# CAN.net
KiCad netlist of a schematic drawn in Altium Designer
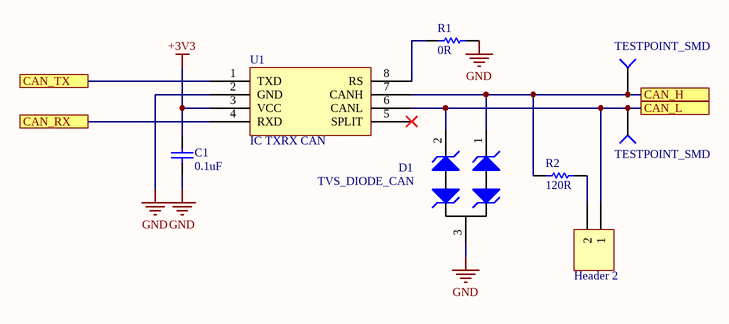
[diagram p0: CAN.SchDoc]

(export (version "E")
  (design (tool "Eeschema 10.0.6"))
  (components
    (comp (ref "1")
      (value "Header 2")
      (footprint "HDR1X2")
      (description "Header, 2-Pin")
      (fields (field (name "PUBLISHER") "Altium Limited"))
      (libsource (lib "Miscellaneous Connectors") (part "Header 2"))
    )
    (comp (ref "C1")
      (value "0.1uF")
      (footprint "CAPC0603(1608)55_N")
      (description "CAP CER 0.1UF 16V X7R 0603")
      (fields (field (name "PART NUMBER") "CC0603KRX7R7BB104") (field (name "MANUFACTURER") "Yageo"))
      (libsource (lib "UWRT_Schematic_Library_2019") (part "CAP_0.1uF_16V_0603"))
    )
    (comp (ref "D1")
      (value "TVS_DIODE_CAN")
      (footprint "TVS_DIODE_CAN")
      (description "TVS DIODE 24V 41V SOT323-3")
      (fields (field (name "PART NUMBER") "PESD2CAN,215") (field (name "MANUFACTURER") "Nexperia USA Inc."))
      (libsource (lib "UWRT_Schematic_Library_2019") (part "TVS_DIODE_CAN"))
    )
    (comp (ref "R1")
      (value "0R")
      (footprint "RESC0603(1608)_N")
      (description "RES SMD 0 OHM JUMPER 1/10W 0603")
      (fields (field (name "MANUFACTURER") "Yageo") (field (name "Comment") "RES_0R_0603"))
      (libsource (lib "UWRT_Schematic_Library_2019") (part "RES_0R_0603"))
    )
    (comp (ref "R2")
      (value "120R")
      (footprint "RESC0603(1608)_N")
      (description "RES SMD 120 OHM 5% 1/10W 0603")
      (fields (field (name "MANUFACTURER") "Yageo") (field (name "TOLERANCE") "5%"))
      (libsource (lib "UWRT_Schematic_Library_2019") (part "RES_120R_0603"))
    )
    (comp (ref "TP1")
      (value "TESTPOINT_SMD")
      (footprint "TESTPOINT")
      (libsource (lib "UWRT_Schematic_Library_2019") (part "TESTPOINT_SMD"))
    )
    (comp (ref "TP2")
      (value "TESTPOINT_SMD")
      (footprint "TESTPOINT")
      (libsource (lib "UWRT_Schematic_Library_2019") (part "TESTPOINT_SMD"))
    )
    (comp (ref "U1")
      (value "IC TXRX CAN")
      (footprint "LTC2875")
      (description "IC TXRX CAN 4MBPS 8SO")
      (fields
        (field (name "MANUFACTURER") "Linear Technologies")
        (field (name "PART NUMBER") "LTC2875IS8#PBF")
      )
      (libsource (lib "UWRT_Schematic_Library_2019") (part "LTC2875"))
    )
  )
  (nets
    (net (code "1") (name "+3V3") (class "Default")
      (node (ref "C1") (pin "2") (pinfunction "2_2") (pintype "passive"))
      (node (ref "U1") (pin "3") (pinfunction "VCC_3") (pintype "passive"))
    )
    (net (code "2") (name "/CAN_H") (class "Default")
      (node (ref "D1") (pin "1") (pinfunction "1_1") (pintype "passive"))
      (node (ref "R2") (pin "1") (pinfunction "1_1") (pintype "passive"))
      (node (ref "TP1") (pin "1") (pinfunction "=value_1") (pintype "passive"))
      (node (ref "U1") (pin "7") (pinfunction "CANH_7") (pintype "passive"))
    )
    (net (code "3") (name "/CAN_L") (class "Default")
      (node (ref "1") (pin "1") (pinfunction "1_1") (pintype "passive"))
      (node (ref "D1") (pin "2") (pinfunction "2_2") (pintype "passive"))
      (node (ref "TP2") (pin "1") (pinfunction "=value_1") (pintype "passive"))
      (node (ref "U1") (pin "6") (pinfunction "CANL_6") (pintype "passive"))
    )
    (net (code "4") (name "/CAN_RX") (class "Default")
      (node (ref "U1") (pin "4") (pinfunction "RXD_4") (pintype "passive"))
    )
    (net (code "5") (name "/CAN_TX") (class "Default")
      (node (ref "U1") (pin "1") (pinfunction "TXD_1") (pintype "passive"))
    )
    (net (code "6") (name "GND") (class "Default")
      (node (ref "C1") (pin "1") (pinfunction "1_1") (pintype "passive"))
      (node (ref "D1") (pin "3") (pinfunction "3_3") (pintype "passive"))
      (node (ref "R1") (pin "2") (pinfunction "2_2") (pintype "passive"))
      (node (ref "U1") (pin "2") (pinfunction "GND_2") (pintype "passive"))
    )
    (net (code "7") (name "Net-(1-Pad2)") (class "Default")
      (node (ref "1") (pin "2") (pinfunction "2_2") (pintype "passive"))
      (node (ref "R2") (pin "2") (pinfunction "2_2") (pintype "passive"))
    )
    (net (code "8") (name "Net-(U1-RS)") (class "Default")
      (node (ref "R1") (pin "1") (pinfunction "1_1") (pintype "passive"))
      (node (ref "U1") (pin "8") (pinfunction "RS_8") (pintype "passive"))
    )
    (net (code "9") (name "unconnected-(U1-SPLIT-Pad5)") (class "Default")
      (node (ref "U1") (pin "5") (pinfunction "SPLIT_5") (pintype "passive+no_connect"))
    )
  )
)
